# interface1.net
KiCad netlist of a schematic drawn in Altium Designer
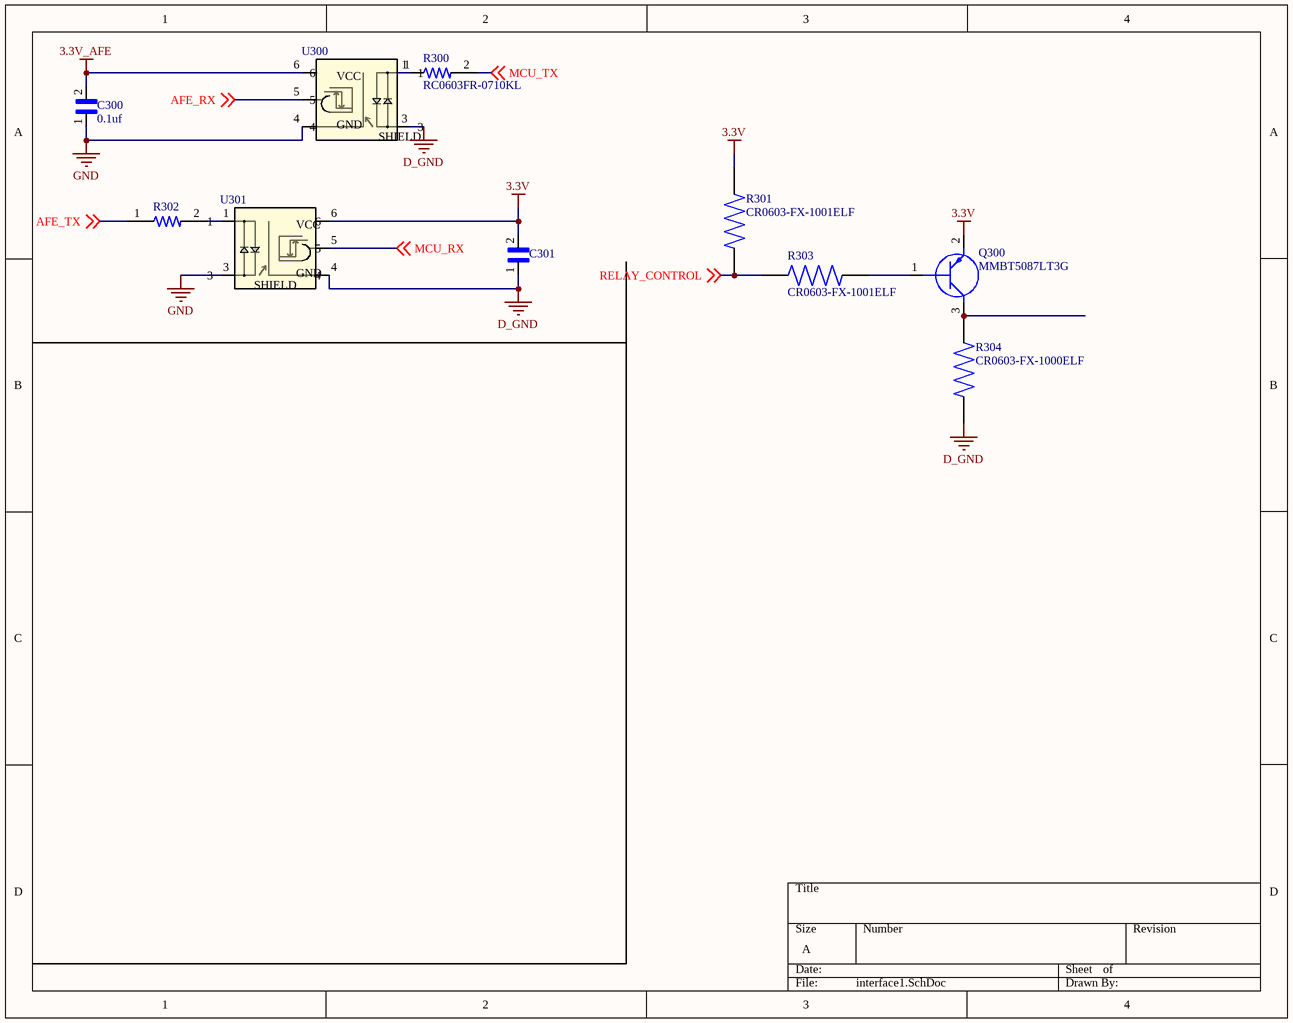
[diagram p0: interface1.SchDoc]

(export (version "E")
  (design (tool "Eeschema 10.0.6"))
  (components
    (comp (ref "C300")
      (value "0.1uf")
      (footprint "CAPC1608X90N")
      (description "Cap Ceramic 0.1uF 25V Y5V -20% to 80% SMD 0603 85C T/R")
      (fields (field (name "MP") "06033G104ZAT4A") (field (name "MF") "{'manufacturer': u'AVX'}"))
      (libsource (lib "SnapEDA_Library") (part "06033G104ZAT4A"))
    )
    (comp (ref "C301")
      (value "06033G104ZAT4A")
      (footprint "CAPC1608X90N")
      (description "Cap Ceramic 0.1uF 25V Y5V -20% to 80% SMD 0603 85C T/R")
      (fields (field (name "MF") "{'manufacturer': u'AVX'}"))
      (libsource (lib "SnapEDA_Library") (part "06033G104ZAT4A"))
    )
    (comp (ref "Q300")
      (value "MMBT5087LT3G")
      (footprint "SOT96P237X111-3N")
      (description "Transistor BJT PNP")
      (fields (field (name "MOUSER PART NUMBER") "863-MMBT5087LT3G"))
      (libsource (lib "*") (part "MMBT5087LT3G"))
    )
    (comp (ref "R300")
      (value "RC0603FR-0710KL")
      (footprint "RESC1607X60N - duplicate")
      (description "YAGEO RC0603FR-0710KL / RESISTOR 10K 1/10W 1% 0603 YAG")
      (fields (field (name "MF") "{'manufacturer': u'Yageo'}"))
      (libsource (lib "SnapEDA_Library") (part "RC0603FR-0710KL"))
    )
    (comp (ref "R301")
      (value "CR0603-FX-1001ELF")
      (footprint "RESC1608X55N - duplicate")
      (description "Resistor; Thick Film; Res 1 Kilohms; Pwr-Rtg 0.1 W; Tol 1%; SMT; 0603")
      (fields (field (name "MF") "{'manufacturer': u'Bourns'}"))
      (libsource (lib "SnapEDA_Library") (part "CR0603-FX-1001ELF"))
    )
    (comp (ref "R302")
      (value "RC0603FR-0710KL")
      (footprint "RESC1607X60N - duplicate")
      (description "YAGEO RC0603FR-0710KL / RESISTOR 10K 1/10W 1% 0603 YAG")
      (fields (field (name "MF") "{'manufacturer': u'Yageo'}"))
      (libsource (lib "SnapEDA_Library") (part "RC0603FR-0710KL"))
    )
    (comp (ref "R303")
      (value "CR0603-FX-1001ELF")
      (footprint "RESC1608X55N - duplicate")
      (description "Resistor; Thick Film; Res 1 Kilohms; Pwr-Rtg 0.1 W; Tol 1%; SMT; 0603")
      (fields (field (name "MF") "{'manufacturer': u'Bourns'}"))
      (libsource (lib "SnapEDA_Library") (part "CR0603-FX-1001ELF"))
    )
    (comp (ref "R304")
      (value "CR0603-FX-1000ELF")
      (footprint "RESC1608X55N - duplicate")
      (description "SMD 0603 thick film resistor 100R 1%")
      (fields (field (name "MF") "{'manufacturer': u'Bourns'}"))
      (libsource (lib "SnapEDA_Library") (part "CR0603-FX-1000ELF"))
    )
    (comp (ref "U300")
      (value "TLP2395")
      (footprint "5pin SO6_TOS")
      (description "No Description Available")
      (fields (field (name "COPYRIGHT") "Copyright (C) 2022 Ultra Librarian. All rights reserved."))
      (libsource (lib "TLP2395") (part "TLP2395"))
    )
    (comp (ref "U301")
      (value "TLP2395")
      (footprint "5pin SO6_TOS")
      (description "No Description Available")
      (fields (field (name "COPYRIGHT") "Copyright (C) 2022 Ultra Librarian. All rights reserved."))
      (libsource (lib "") (part "TLP2395_1"))
    )
  )
  (nets
    (net (code "1") (name "3.3V") (class "Default")
      (node (ref "C301") (pin "2") (pinfunction "2_2") (pintype "passive"))
      (node (ref "Q300") (pin "2") (pinfunction "E_2") (pintype "passive"))
      (node (ref "R301") (pin "2") (pinfunction "2_2") (pintype "passive"))
      (node (ref "U301") (pin "6") (pinfunction "6_6") (pintype "passive"))
    )
    (net (code "2") (name "3.3V_AFE") (class "Default")
      (node (ref "C300") (pin "2") (pinfunction "2_2") (pintype "passive"))
      (node (ref "U300") (pin "6") (pinfunction "6_6") (pintype "passive"))
    )
    (net (code "3") (name "AFE_RX") (class "Default")
      (node (ref "U300") (pin "5") (pinfunction "5_5") (pintype "output"))
    )
    (net (code "4") (name "AFE_TX") (class "Default")
      (node (ref "R302") (pin "1") (pinfunction "1_1") (pintype "passive"))
    )
    (net (code "5") (name "D_GND") (class "Default")
      (node (ref "C301") (pin "1") (pinfunction "1_1") (pintype "passive"))
      (node (ref "R304") (pin "1") (pinfunction "1_1") (pintype "passive"))
      (node (ref "U300") (pin "3") (pinfunction "3_3") (pintype "passive"))
      (node (ref "U301") (pin "4") (pinfunction "4_4") (pintype "passive"))
    )
    (net (code "6") (name "GND") (class "Default")
      (node (ref "C300") (pin "1") (pinfunction "1_1") (pintype "passive"))
      (node (ref "U300") (pin "4") (pinfunction "4_4") (pintype "passive"))
      (node (ref "U301") (pin "3") (pinfunction "3_3") (pintype "passive"))
    )
    (net (code "7") (name "MCU_RX") (class "Default")
      (node (ref "U301") (pin "5") (pinfunction "5_5") (pintype "output"))
    )
    (net (code "8") (name "MCU_TX") (class "Default")
      (node (ref "R300") (pin "2") (pinfunction "2_2") (pintype "passive"))
    )
    (net (code "9") (name "Net-(Q300-B)") (class "Default")
      (node (ref "Q300") (pin "1") (pinfunction "B_1") (pintype "passive"))
      (node (ref "R303") (pin "2") (pinfunction "2_2") (pintype "passive"))
    )
    (net (code "10") (name "Net-(Q300-C)") (class "Default")
      (node (ref "Q300") (pin "3") (pinfunction "C_3") (pintype "passive"))
      (node (ref "R304") (pin "2") (pinfunction "2_2") (pintype "passive"))
    )
    (net (code "11") (name "Net-(R300-Pad1)") (class "Default")
      (node (ref "R300") (pin "1") (pinfunction "1_1") (pintype "passive"))
      (node (ref "U300") (pin "1") (pinfunction "1_1") (pintype "passive"))
    )
    (net (code "12") (name "Net-(R302-Pad2)") (class "Default")
      (node (ref "R302") (pin "2") (pinfunction "2_2") (pintype "passive"))
      (node (ref "U301") (pin "1") (pinfunction "1_1") (pintype "passive"))
    )
    (net (code "13") (name "RELAY_CONTROL") (class "Default")
      (node (ref "R301") (pin "1") (pinfunction "1_1") (pintype "passive"))
      (node (ref "R303") (pin "1") (pinfunction "1_1") (pintype "passive"))
    )
  )
)
